# CPU.net
KiCad netlist of a schematic drawn in Altium Designer
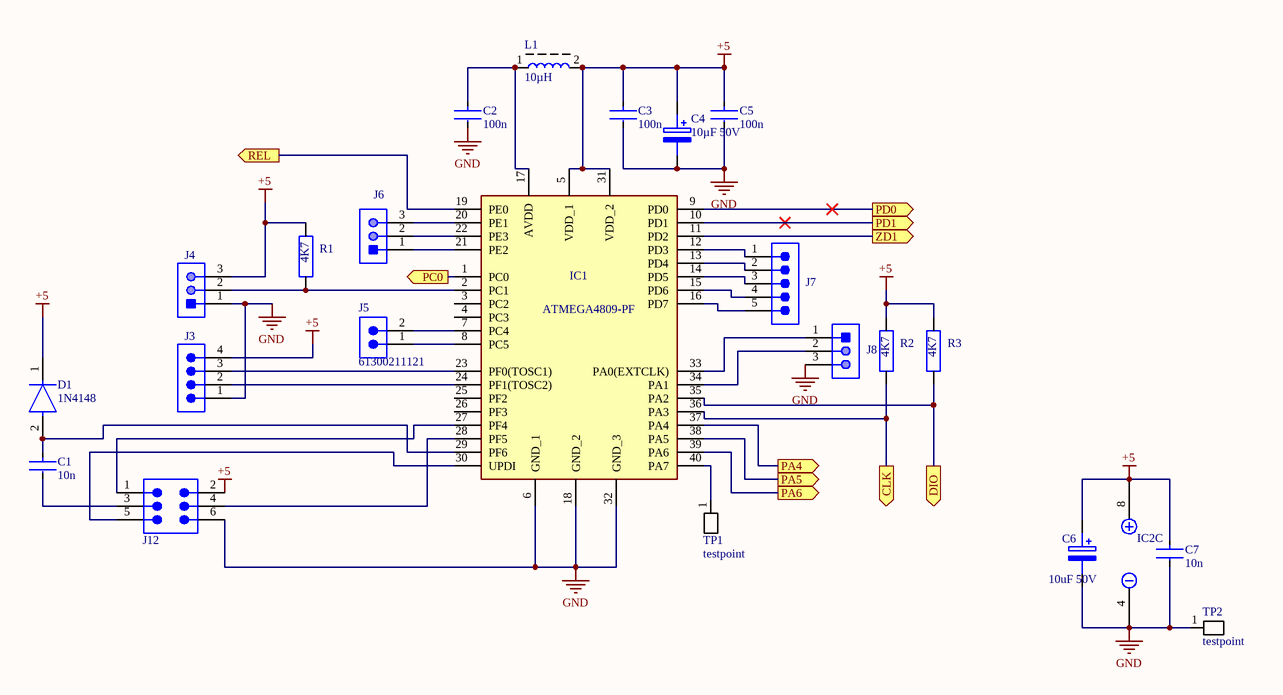
[diagram p0: CPU.SchDoc]

(export (version "E")
  (design (tool "Eeschema 10.0.6"))
  (components
    (comp (ref "C1")
      (value "10n")
      (footprint "FP-C0805C-DN-IPC_A")
      (description "CAP CER 10000PF 200V X7R 0805")
      (fields
        (field (name "OCTOPART") "https://octopart.com/c0805c103k2ractu-kemet-9138347")
        (field (name "MANUFACTURER PART NUMBER") "C0805C103K2RACTU")
      )
      (libsource (lib "Altium Content Vault") (part "b4654b650e69147ec39a6b967a45e02"))
    )
    (comp (ref "C2")
      (value "100n")
      (footprint "FP-C0805C-DN-IPC_B")
      (description "CAP CER 10000PF 200V X7R 0805")
      (fields
        (field (name "OCTOPART") "https://octopart.com/c0805c103k2ractu-kemet-9138347")
        (field (name "MANUFACTURER PART NUMBER") "C0805C103K2RACTU")
      )
      (libsource (lib "Altium Content Vault") (part "b4654b650e69147ec39a6b967a45e02"))
    )
    (comp (ref "C3")
      (value "100n")
      (footprint "FP-C0805C-DN-IPC_A")
      (description "CAP CER 10000PF 200V X7R 0805")
      (fields
        (field (name "OCTOPART") "https://octopart.com/c0805c103k2ractu-kemet-9138347")
        (field (name "MANUFACTURER PART NUMBER") "C0805C103K2RACTU")
      )
      (libsource (lib "Altium Content Vault") (part "b4654b650e69147ec39a6b967a45e02"))
    )
    (comp (ref "C4")
      (value "10µF 50V")
      (footprint "caprad100mil")
      (description "Capacitor Polarised")
      (fields
        (field (name "MANUFACTURER_PART_NUMBER") "T494D227K006AT")
        (field (name "MOUSER PART NUMBER") "80-T494D227K006")
      )
      (libsource (lib "Schlib1") (part "ELCO220uF"))
    )
    (comp (ref "C5")
      (value "100n")
      (footprint "FP-C0805C-DN-IPC_A")
      (description "CAP CER 10000PF 200V X7R 0805")
      (fields
        (field (name "OCTOPART") "https://octopart.com/c0805c103k2ractu-kemet-9138347")
        (field (name "MANUFACTURER PART NUMBER") "C0805C103K2RACTU")
      )
      (libsource (lib "Altium Content Vault") (part "b4654b650e69147ec39a6b967a45e02"))
    )
    (comp (ref "C6")
      (value "10uF 50V")
      (footprint "caprad100mil")
      (description "Capacitor Polarised")
      (fields
        (field (name "MANUFACTURER_PART_NUMBER") "T494D227K006AT")
        (field (name "MOUSER PART NUMBER") "80-T494D227K006")
      )
      (libsource (lib "soldeerstation") (part "ELCO220uF"))
    )
    (comp (ref "C7")
      (value "10n")
      (footprint "FP-C0805C-DN-IPC_A")
      (description "CAP CER 10000PF 200V X7R 0805")
      (fields
        (field (name "OCTOPART") "https://octopart.com/c0805c103k2ractu-kemet-9138347")
        (field (name "MANUFACTURER PART NUMBER") "C0805C103K2RACTU")
      )
      (libsource (lib "Altium Content Vault") (part "b4654b650e69147ec39a6b967a45e02"))
    )
    (comp (ref "D1")
      (value "1N4148")
      (footprint "FP-017AG-MFG")
      (description "DIODE GEN PURP 100V 200MA DO35")
      (fields (field (name "VOLTAGE") "100V"))
      (libsource (lib "1N4148") (part "CMP-07163-000046-1"))
    )
    (comp (ref "IC1")
      (value "ATMEGA4809-PF")
      (footprint "SamacSys:DIP1543W58P254L5175H635Q40N")
      (description "Integrated Circuit")
      (fields (field (name "MOUSER PART NUMBER") "556-ATMEGA4809-PF"))
      (libsource (lib "soldeerstation") (part "ATMEGA4809-PF"))
    )
    (comp (ref "IC2")
      (value "MCP6002-E/P")
      (footprint "DIP8PIN")
      (description "None")
      (libsource (lib "soldeerstation") (part "AMP-OPA-MCP6002-IL8"))
    )
    (comp (ref "J3")
      (value "61300411121")
      (footprint "61300411121")
      (libsource (lib "Altium Content Vault") (part "Header_Male_1R_04P"))
    )
    (comp (ref "J4")
      (value "22-28-4033")
      (footprint "MOLX-22-28-4033_V")
      (description "Male Header, Pitch 2.54 mm, 1 x 3 Position, Height 8.38 mm, Tail Length 3.18 mm, RoHS, Bulk")
      (fields (field (name "MANUFACTURER") "Molex"))
      (libsource (lib "") (part "CN-1P-M-R3_1"))
    )
    (comp (ref "J5")
      (value "61300211121")
      (footprint "61300211121")
      (libsource (lib "Altium Content Vault") (part "Header_Male_1R_02P"))
    )
    (comp (ref "J6")
      (value "22-28-4033")
      (footprint "MOLX-22-28-4033_V")
      (description "Male Header, Pitch 2.54 mm, 1 x 3 Position, Height 8.38 mm, Tail Length 3.18 mm, RoHS, Bulk")
      (fields (field (name "MANUFACTURER") "Molex"))
      (libsource (lib "") (part "CN-1P-M-R3_1"))
    )
    (comp (ref "J7")
      (value "61300511121")
      (footprint "61300511121")
      (libsource (lib "Altium Content Vault") (part "Header_Male_1R_05P"))
    )
    (comp (ref "J8")
      (value "22-28-4033")
      (footprint "MOLX-22-28-4033_V")
      (description "Male Header, Pitch 2.54 mm, 1 x 3 Position, Height 8.38 mm, Tail Length 3.18 mm, RoHS, Bulk")
      (fields (field (name "MANUFACTURER") "Molex"))
      (libsource (lib "Altium Content Vault") (part "CN-1P-M-R3"))
    )
    (comp (ref "J12")
      (value "610106249121")
      (footprint "610106249121")
      (libsource (lib "Altium Content Vault") (part "Header_Male_2R_06P"))
    )
    (comp (ref "L1")
      (value "10µH")
      (footprint "spoelSMD10µH")
      (libsource (lib "soldeerstation") (part "Spoel_1"))
    )
    (comp (ref "R1")
      (value "4K7")
      (footprint "res0805ph")
      (description "Resistor")
      (fields (field (name "MANUFACTURER_PART_NUMBER") "CPF0201D10K2C1"))
      (libsource (lib "soldeerstation") (part "Res"))
    )
    (comp (ref "R2")
      (value "4K7")
      (footprint "res0805ph")
      (description "Resistor")
      (fields (field (name "MANUFACTURER_PART_NUMBER") "CPF0201D10K2C1"))
      (libsource (lib "soldeerstation") (part "Res"))
    )
    (comp (ref "R3")
      (value "4K7")
      (footprint "res0805ph")
      (description "Resistor")
      (fields (field (name "MANUFACTURER_PART_NUMBER") "CPF0201D10K2C1"))
      (libsource (lib "soldeerstation") (part "Res"))
    )
    (comp (ref "TP1")
      (value "testpoint")
      (footprint "testpin")
      (libsource (lib "soldeerstation") (part "testpoint"))
    )
    (comp (ref "TP2")
      (value "testpoint")
      (footprint "testpin")
      (libsource (lib "soldeerstation") (part "testpoint"))
    )
  )
  (nets
    (net (code "1") (name "+5") (class "Default")
      (node (ref "C3") (pin "1") (pinfunction "1_1") (pintype "passive"))
      (node (ref "C4") (pin "1") (pinfunction "+_1") (pintype "passive"))
      (node (ref "C5") (pin "1") (pinfunction "1_1") (pintype "passive"))
      (node (ref "C6") (pin "1") (pinfunction "+_1") (pintype "passive"))
      (node (ref "C7") (pin "1") (pinfunction "1_1") (pintype "passive"))
      (node (ref "D1") (pin "1") (pinfunction "C_1") (pintype "passive"))
      (node (ref "IC1") (pin "31") (pinfunction "VDD_2_31") (pintype "passive"))
      (node (ref "IC1") (pin "5") (pinfunction "VDD_1_5") (pintype "passive"))
      (node (ref "IC2") (pin "8") (pinfunction "8_8") (pintype "passive"))
      (node (ref "J12") (pin "2") (pinfunction "2_2") (pintype "passive"))
      (node (ref "J3") (pin "4") (pinfunction "4_4") (pintype "passive"))
      (node (ref "J4") (pin "3") (pinfunction "3_3") (pintype "passive"))
      (node (ref "L1") (pin "2") (pinfunction "2_2") (pintype "passive"))
      (node (ref "R1") (pin "1") (pinfunction "1_1") (pintype "passive"))
      (node (ref "R2") (pin "1") (pinfunction "1_1") (pintype "passive"))
      (node (ref "R3") (pin "1") (pinfunction "1_1") (pintype "passive"))
    )
    (net (code "2") (name "/CLK") (class "Default")
      (node (ref "IC1") (pin "36") (pinfunction "PA3_36") (pintype "passive"))
      (node (ref "R2") (pin "2") (pinfunction "2_2") (pintype "passive"))
    )
    (net (code "3") (name "/DIO") (class "Default")
      (node (ref "IC1") (pin "35") (pinfunction "PA2_35") (pintype "passive"))
      (node (ref "R3") (pin "2") (pinfunction "2_2") (pintype "passive"))
    )
    (net (code "4") (name "/PA4") (class "Default")
      (node (ref "IC1") (pin "37") (pinfunction "PA4_37") (pintype "passive"))
    )
    (net (code "5") (name "/PA5") (class "Default")
      (node (ref "IC1") (pin "38") (pinfunction "PA5_38") (pintype "passive"))
    )
    (net (code "6") (name "/PA6") (class "Default")
      (node (ref "IC1") (pin "39") (pinfunction "PA6_39") (pintype "passive"))
    )
    (net (code "7") (name "/PC0") (class "Default")
      (node (ref "IC1") (pin "1") (pinfunction "PC0_1") (pintype "passive"))
    )
    (net (code "8") (name "/PD0") (class "Default")
      (node (ref "IC1") (pin "9") (pinfunction "PD0_9") (pintype "passive"))
    )
    (net (code "9") (name "/PD1") (class "Default")
      (node (ref "IC1") (pin "10") (pinfunction "PD1_10") (pintype "passive"))
    )
    (net (code "10") (name "/REL") (class "Default")
      (node (ref "IC1") (pin "19") (pinfunction "PE0_19") (pintype "passive"))
    )
    (net (code "11") (name "/ZD1") (class "Default")
      (node (ref "IC1") (pin "11") (pinfunction "PD2_11") (pintype "passive"))
    )
    (net (code "12") (name "GND") (class "Default")
      (node (ref "C2") (pin "2") (pinfunction "2_2") (pintype "passive"))
      (node (ref "C3") (pin "2") (pinfunction "2_2") (pintype "passive"))
      (node (ref "C4") (pin "2") (pinfunction "-_2") (pintype "passive"))
      (node (ref "C5") (pin "2") (pinfunction "2_2") (pintype "passive"))
      (node (ref "C6") (pin "2") (pinfunction "-_2") (pintype "passive"))
      (node (ref "C7") (pin "2") (pinfunction "2_2") (pintype "passive"))
      (node (ref "IC1") (pin "18") (pinfunction "GND_2_18") (pintype "passive"))
      (node (ref "IC1") (pin "32") (pinfunction "GND_3_32") (pintype "passive"))
      (node (ref "IC1") (pin "6") (pinfunction "GND_1_6") (pintype "passive"))
      (node (ref "IC2") (pin "4") (pinfunction "4_4") (pintype "passive"))
      (node (ref "J12") (pin "6") (pinfunction "6_6") (pintype "passive"))
      (node (ref "J3") (pin "1") (pinfunction "1_1") (pintype "passive"))
      (node (ref "J4") (pin "1") (pinfunction "1_1") (pintype "passive"))
      (node (ref "J8") (pin "3") (pinfunction "3_3") (pintype "passive"))
      (node (ref "TP2") (pin "1") (pinfunction "TP_1") (pintype "passive"))
    )
    (net (code "13") (name "Net-(C1-Pad2)") (class "Default")
      (node (ref "C1") (pin "2") (pinfunction "2_2") (pintype "passive"))
      (node (ref "J12") (pin "3") (pinfunction "3_3") (pintype "passive"))
    )
    (net (code "14") (name "Net-(D1-A)") (class "Default")
      (node (ref "C1") (pin "1") (pinfunction "1_1") (pintype "passive"))
      (node (ref "D1") (pin "2") (pinfunction "A_2") (pintype "passive"))
      (node (ref "IC1") (pin "29") (pinfunction "PF6_29") (pintype "passive"))
    )
    (net (code "15") (name "Net-(IC1-AVDD)") (class "Default")
      (node (ref "C2") (pin "1") (pinfunction "1_1") (pintype "passive"))
      (node (ref "IC1") (pin "17") (pinfunction "AVDD_17") (pintype "passive"))
      (node (ref "L1") (pin "1") (pinfunction "1_1") (pintype "passive"))
    )
    (net (code "16") (name "Net-(IC1-PA0(EXTCLK))") (class "Default")
      (node (ref "IC1") (pin "33") (pinfunction "PA0(EXTCLK)_33") (pintype "passive"))
      (node (ref "J8") (pin "1") (pinfunction "1_1") (pintype "passive"))
    )
    (net (code "17") (name "Net-(IC1-PA1)") (class "Default")
      (node (ref "IC1") (pin "34") (pinfunction "PA1_34") (pintype "passive"))
      (node (ref "J8") (pin "2") (pinfunction "2_2") (pintype "passive"))
    )
    (net (code "18") (name "Net-(IC1-PA7)") (class "Default")
      (node (ref "IC1") (pin "40") (pinfunction "PA7_40") (pintype "passive"))
      (node (ref "TP1") (pin "1") (pinfunction "TP_1") (pintype "passive"))
    )
    (net (code "19") (name "Net-(IC1-PC1)") (class "Default")
      (node (ref "IC1") (pin "2") (pinfunction "PC1_2") (pintype "passive"))
      (node (ref "J4") (pin "2") (pinfunction "2_2") (pintype "passive"))
      (node (ref "R1") (pin "2") (pinfunction "2_2") (pintype "passive"))
    )
    (net (code "20") (name "Net-(IC1-PC4)") (class "Default")
      (node (ref "IC1") (pin "7") (pinfunction "PC4_7") (pintype "passive"))
      (node (ref "J5") (pin "2") (pinfunction "2_2") (pintype "passive"))
    )
    (net (code "21") (name "Net-(IC1-PC5)") (class "Default")
      (node (ref "IC1") (pin "8") (pinfunction "PC5_8") (pintype "passive"))
      (node (ref "J5") (pin "1") (pinfunction "1_1") (pintype "passive"))
    )
    (net (code "22") (name "Net-(IC1-PD3)") (class "Default")
      (node (ref "IC1") (pin "12") (pinfunction "PD3_12") (pintype "passive"))
      (node (ref "J7") (pin "1") (pinfunction "1_1") (pintype "passive"))
    )
    (net (code "23") (name "Net-(IC1-PD4)") (class "Default")
      (node (ref "IC1") (pin "13") (pinfunction "PD4_13") (pintype "passive"))
      (node (ref "J7") (pin "2") (pinfunction "2_2") (pintype "passive"))
    )
    (net (code "24") (name "Net-(IC1-PD5)") (class "Default")
      (node (ref "IC1") (pin "14") (pinfunction "PD5_14") (pintype "passive"))
      (node (ref "J7") (pin "3") (pinfunction "3_3") (pintype "passive"))
    )
    (net (code "25") (name "Net-(IC1-PD6)") (class "Default")
      (node (ref "IC1") (pin "15") (pinfunction "PD6_15") (pintype "passive"))
      (node (ref "J7") (pin "4") (pinfunction "4_4") (pintype "passive"))
    )
    (net (code "26") (name "Net-(IC1-PD7)") (class "Default")
      (node (ref "IC1") (pin "16") (pinfunction "PD7_16") (pintype "passive"))
      (node (ref "J7") (pin "5") (pinfunction "5_5") (pintype "passive"))
    )
    (net (code "27") (name "Net-(IC1-PE1)") (class "Default")
      (node (ref "IC1") (pin "20") (pinfunction "PE1_20") (pintype "passive"))
      (node (ref "J6") (pin "3") (pinfunction "3_3") (pintype "passive"))
    )
    (net (code "28") (name "Net-(IC1-PE2)") (class "Default")
      (node (ref "IC1") (pin "21") (pinfunction "PE2_21") (pintype "passive"))
      (node (ref "J6") (pin "1") (pinfunction "1_1") (pintype "passive"))
    )
    (net (code "29") (name "Net-(IC1-PE3)") (class "Default")
      (node (ref "IC1") (pin "22") (pinfunction "PE3_22") (pintype "passive"))
      (node (ref "J6") (pin "2") (pinfunction "2_2") (pintype "passive"))
    )
    (net (code "30") (name "Net-(IC1-PF0(TOSC1))") (class "Default")
      (node (ref "IC1") (pin "23") (pinfunction "PF0(TOSC1)_23") (pintype "passive"))
      (node (ref "J3") (pin "3") (pinfunction "3_3") (pintype "passive"))
    )
    (net (code "31") (name "Net-(IC1-PF1(TOSC2))") (class "Default")
      (node (ref "IC1") (pin "24") (pinfunction "PF1(TOSC2)_24") (pintype "passive"))
      (node (ref "J3") (pin "2") (pinfunction "2_2") (pintype "passive"))
    )
    (net (code "32") (name "Net-(IC1-PF4)") (class "Default")
      (node (ref "IC1") (pin "27") (pinfunction "PF4_27") (pintype "passive"))
      (node (ref "J12") (pin "1") (pinfunction "1_1") (pintype "passive"))
    )
    (net (code "33") (name "Net-(IC1-PF5)") (class "Default")
      (node (ref "IC1") (pin "28") (pinfunction "PF5_28") (pintype "passive"))
      (node (ref "J12") (pin "4") (pinfunction "4_4") (pintype "passive"))
    )
    (net (code "34") (name "Net-(IC1-UPDI)") (class "Default")
      (node (ref "IC1") (pin "30") (pinfunction "UPDI_30") (pintype "passive"))
      (node (ref "J12") (pin "5") (pinfunction "5_5") (pintype "passive"))
    )
    (net (code "35") (name "unconnected-(IC1-PC2-Pad3)") (class "Default")
      (node (ref "IC1") (pin "3") (pinfunction "PC2_3") (pintype "passive"))
    )
    (net (code "36") (name "unconnected-(IC1-PC3-Pad4)") (class "Default")
      (node (ref "IC1") (pin "4") (pinfunction "PC3_4") (pintype "passive"))
    )
    (net (code "37") (name "unconnected-(IC1-PF2-Pad25)") (class "Default")
      (node (ref "IC1") (pin "25") (pinfunction "PF2_25") (pintype "passive"))
    )
    (net (code "38") (name "unconnected-(IC1-PF3-Pad26)") (class "Default")
      (node (ref "IC1") (pin "26") (pinfunction "PF3_26") (pintype "passive"))
    )
  )
)
